# Chassis_Board.net
KiCad netlist of a schematic drawn in EAGLE
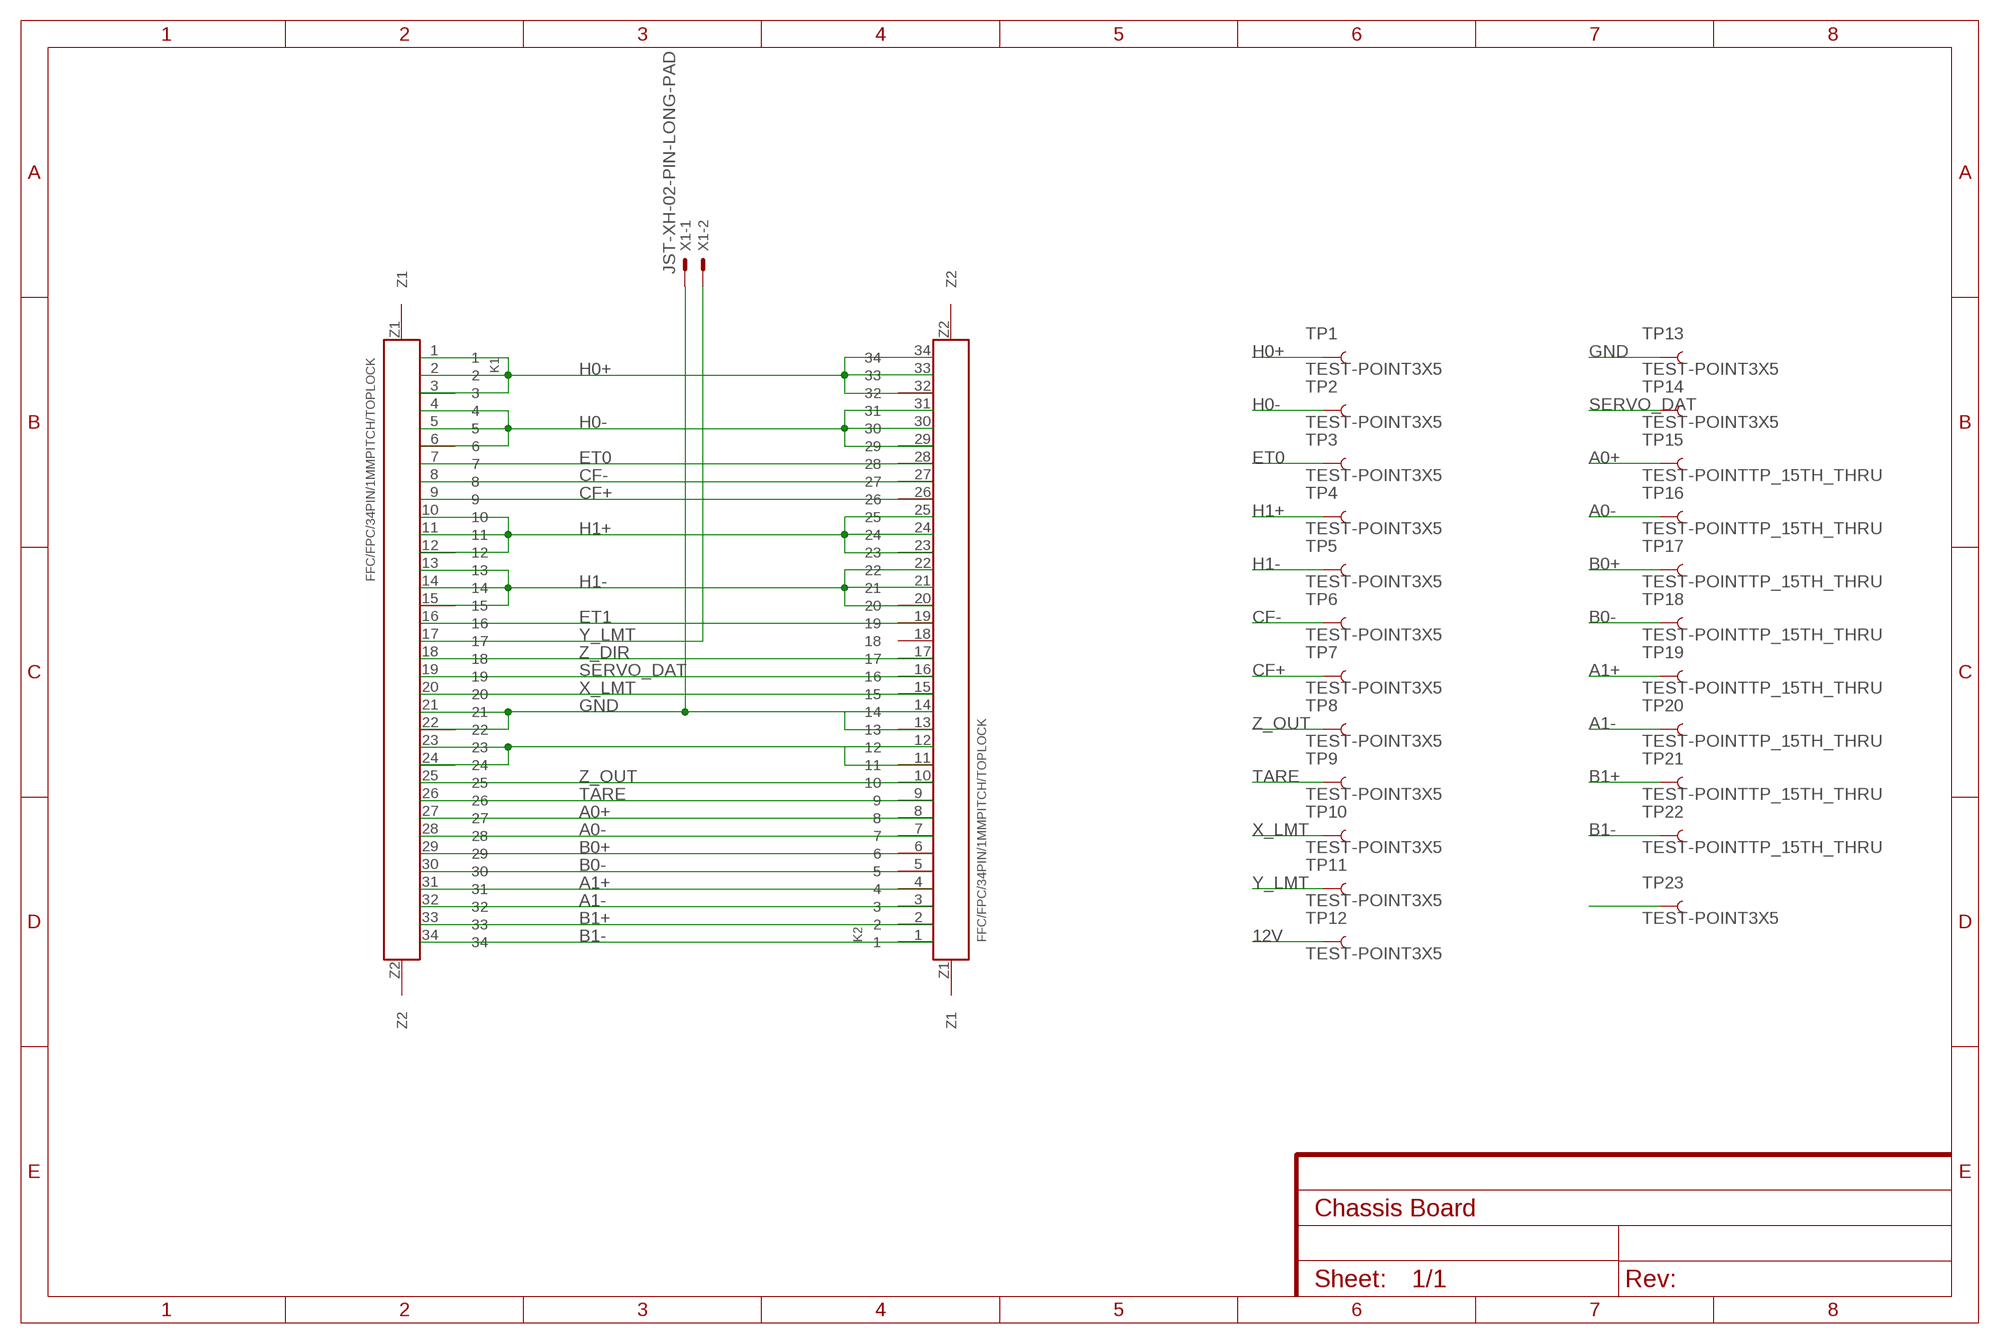
[diagram p0: schematic, sheet 1]

(export (version "E")
  (design (tool "Eeschema 10.0.6"))
  (components
    (comp (ref "K1")
      (value "FFC/FPC/34PIN/1MMPITCH/TOPLOCK")
      (footprint "eagle-import:34PIN_1MMPITCH_FFC_FPC")
      (libsource (lib "eagle-import") (part "FFC/FPC/34PIN/1MMPITCH/TOPLOCK"))
    )
    (comp (ref "K2")
      (value "FFC/FPC/34PIN/1MMPITCH/TOPLOCK")
      (footprint "eagle-import:34PIN_1MMPITCH_FFC_FPC")
      (libsource (lib "eagle-import") (part "FFC/FPC/34PIN/1MMPITCH/TOPLOCK"))
    )
    (comp (ref "TP1")
      (value "TEST-POINT3X5")
      (footprint "eagle-import:PAD.03X.05")
      (libsource (lib "eagle-import") (part "TEST-POINT3X5"))
    )
    (comp (ref "TP2")
      (value "TEST-POINT3X5")
      (footprint "eagle-import:PAD.03X.05")
      (libsource (lib "eagle-import") (part "TEST-POINT3X5"))
    )
    (comp (ref "TP3")
      (value "TEST-POINT3X5")
      (footprint "eagle-import:PAD.03X.05")
      (libsource (lib "eagle-import") (part "TEST-POINT3X5"))
    )
    (comp (ref "TP4")
      (value "TEST-POINT3X5")
      (footprint "eagle-import:PAD.03X.05")
      (libsource (lib "eagle-import") (part "TEST-POINT3X5"))
    )
    (comp (ref "TP5")
      (value "TEST-POINT3X5")
      (footprint "eagle-import:PAD.03X.05")
      (libsource (lib "eagle-import") (part "TEST-POINT3X5"))
    )
    (comp (ref "TP6")
      (value "TEST-POINT3X5")
      (footprint "eagle-import:PAD.03X.05")
      (libsource (lib "eagle-import") (part "TEST-POINT3X5"))
    )
    (comp (ref "TP7")
      (value "TEST-POINT3X5")
      (footprint "eagle-import:PAD.03X.05")
      (libsource (lib "eagle-import") (part "TEST-POINT3X5"))
    )
    (comp (ref "TP8")
      (value "TEST-POINT3X5")
      (footprint "eagle-import:PAD.03X.05")
      (libsource (lib "eagle-import") (part "TEST-POINT3X5"))
    )
    (comp (ref "TP9")
      (value "TEST-POINT3X5")
      (footprint "eagle-import:PAD.03X.05")
      (libsource (lib "eagle-import") (part "TEST-POINT3X5"))
    )
    (comp (ref "TP10")
      (value "TEST-POINT3X5")
      (footprint "eagle-import:PAD.03X.05")
      (libsource (lib "eagle-import") (part "TEST-POINT3X5"))
    )
    (comp (ref "TP11")
      (value "TEST-POINT3X5")
      (footprint "eagle-import:PAD.03X.05")
      (libsource (lib "eagle-import") (part "TEST-POINT3X5"))
    )
    (comp (ref "TP12")
      (value "TEST-POINT3X5")
      (footprint "eagle-import:PAD.03X.05")
      (libsource (lib "eagle-import") (part "TEST-POINT3X5"))
    )
    (comp (ref "TP13")
      (value "TEST-POINT3X5")
      (footprint "eagle-import:PAD.03X.05")
      (libsource (lib "eagle-import") (part "TEST-POINT3X5"))
    )
    (comp (ref "TP14")
      (value "TEST-POINT3X5")
      (footprint "eagle-import:PAD.03X.05")
      (libsource (lib "eagle-import") (part "TEST-POINT3X5"))
    )
    (comp (ref "TP15")
      (value "TEST-POINTTP_15TH_THRU")
      (footprint "eagle-import:TP_15TH")
      (libsource (lib "eagle-import") (part "TEST-POINTTP_15TH_THRU"))
    )
    (comp (ref "TP16")
      (value "TEST-POINTTP_15TH_THRU")
      (footprint "eagle-import:TP_15TH")
      (libsource (lib "eagle-import") (part "TEST-POINTTP_15TH_THRU"))
    )
    (comp (ref "TP17")
      (value "TEST-POINTTP_15TH_THRU")
      (footprint "eagle-import:TP_15TH")
      (libsource (lib "eagle-import") (part "TEST-POINTTP_15TH_THRU"))
    )
    (comp (ref "TP18")
      (value "TEST-POINTTP_15TH_THRU")
      (footprint "eagle-import:TP_15TH")
      (libsource (lib "eagle-import") (part "TEST-POINTTP_15TH_THRU"))
    )
    (comp (ref "TP19")
      (value "TEST-POINTTP_15TH_THRU")
      (footprint "eagle-import:TP_15TH")
      (libsource (lib "eagle-import") (part "TEST-POINTTP_15TH_THRU"))
    )
    (comp (ref "TP20")
      (value "TEST-POINTTP_15TH_THRU")
      (footprint "eagle-import:TP_15TH")
      (libsource (lib "eagle-import") (part "TEST-POINTTP_15TH_THRU"))
    )
    (comp (ref "TP21")
      (value "TEST-POINTTP_15TH_THRU")
      (footprint "eagle-import:TP_15TH")
      (libsource (lib "eagle-import") (part "TEST-POINTTP_15TH_THRU"))
    )
    (comp (ref "TP22")
      (value "TEST-POINTTP_15TH_THRU")
      (footprint "eagle-import:TP_15TH")
      (libsource (lib "eagle-import") (part "TEST-POINTTP_15TH_THRU"))
    )
    (comp (ref "TP23")
      (value "TEST-POINT3X5")
      (footprint "eagle-import:PAD.03X.05")
      (libsource (lib "eagle-import") (part "TEST-POINT3X5"))
    )
    (comp (ref "X1")
      (value "JST-XH-02-PIN-LONG-PAD")
      (footprint "eagle-import:JST-XH-02-PACKAGE-LONG-PAD")
      (libsource (lib "eagle-import") (part "JST-XH-02-PIN-LONG-PAD"))
    )
  )
  (nets
    (net (code "1") (name "/12V") (class "Default")
      (node (ref "K1") (pin "23") (pinfunction "23_23") (pintype "bidirectional"))
      (node (ref "K1") (pin "24") (pinfunction "24_24") (pintype "bidirectional"))
      (node (ref "K2") (pin "11") (pinfunction "11_11") (pintype "bidirectional"))
      (node (ref "K2") (pin "12") (pinfunction "12_12") (pintype "bidirectional"))
      (node (ref "TP12") (pin "P$1") (pinfunction "1_P$1") (pintype "bidirectional"))
    )
    (net (code "2") (name "/A0+") (class "Default")
      (node (ref "K1") (pin "27") (pinfunction "27_27") (pintype "bidirectional"))
      (node (ref "K2") (pin "8") (pinfunction "8_8") (pintype "bidirectional"))
      (node (ref "TP15") (pin "P$1") (pinfunction "1_P$1") (pintype "bidirectional"))
    )
    (net (code "3") (name "/A0-") (class "Default")
      (node (ref "K1") (pin "28") (pinfunction "28_28") (pintype "bidirectional"))
      (node (ref "K2") (pin "7") (pinfunction "7_7") (pintype "bidirectional"))
      (node (ref "TP16") (pin "P$1") (pinfunction "1_P$1") (pintype "bidirectional"))
    )
    (net (code "4") (name "/A1+") (class "Default")
      (node (ref "K1") (pin "31") (pinfunction "31_31") (pintype "bidirectional"))
      (node (ref "K2") (pin "4") (pinfunction "4_4") (pintype "bidirectional"))
      (node (ref "TP19") (pin "P$1") (pinfunction "1_P$1") (pintype "bidirectional"))
    )
    (net (code "5") (name "/A1-") (class "Default")
      (node (ref "K1") (pin "32") (pinfunction "32_32") (pintype "bidirectional"))
      (node (ref "K2") (pin "3") (pinfunction "3_3") (pintype "bidirectional"))
      (node (ref "TP20") (pin "P$1") (pinfunction "1_P$1") (pintype "bidirectional"))
    )
    (net (code "6") (name "/B0+") (class "Default")
      (node (ref "K1") (pin "29") (pinfunction "29_29") (pintype "bidirectional"))
      (node (ref "K2") (pin "6") (pinfunction "6_6") (pintype "bidirectional"))
      (node (ref "TP17") (pin "P$1") (pinfunction "1_P$1") (pintype "bidirectional"))
    )
    (net (code "7") (name "/B0-") (class "Default")
      (node (ref "K1") (pin "30") (pinfunction "30_30") (pintype "bidirectional"))
      (node (ref "K2") (pin "5") (pinfunction "5_5") (pintype "bidirectional"))
      (node (ref "TP18") (pin "P$1") (pinfunction "1_P$1") (pintype "bidirectional"))
    )
    (net (code "8") (name "/B1+") (class "Default")
      (node (ref "K1") (pin "33") (pinfunction "33_33") (pintype "bidirectional"))
      (node (ref "K2") (pin "2") (pinfunction "2_2") (pintype "bidirectional"))
      (node (ref "TP21") (pin "P$1") (pinfunction "1_P$1") (pintype "bidirectional"))
    )
    (net (code "9") (name "/B1-") (class "Default")
      (node (ref "K1") (pin "34") (pinfunction "34_34") (pintype "bidirectional"))
      (node (ref "K2") (pin "1") (pinfunction "1_1") (pintype "bidirectional"))
      (node (ref "TP22") (pin "P$1") (pinfunction "1_P$1") (pintype "bidirectional"))
    )
    (net (code "10") (name "/CF+") (class "Default")
      (node (ref "K1") (pin "9") (pinfunction "9_9") (pintype "bidirectional"))
      (node (ref "K2") (pin "26") (pinfunction "26_26") (pintype "bidirectional"))
      (node (ref "TP7") (pin "P$1") (pinfunction "1_P$1") (pintype "bidirectional"))
    )
    (net (code "11") (name "/CF-") (class "Default")
      (node (ref "K1") (pin "8") (pinfunction "8_8") (pintype "bidirectional"))
      (node (ref "K2") (pin "27") (pinfunction "27_27") (pintype "bidirectional"))
      (node (ref "TP6") (pin "P$1") (pinfunction "1_P$1") (pintype "bidirectional"))
    )
    (net (code "12") (name "/ET0") (class "Default")
      (node (ref "K1") (pin "7") (pinfunction "7_7") (pintype "bidirectional"))
      (node (ref "K2") (pin "28") (pinfunction "28_28") (pintype "bidirectional"))
      (node (ref "TP3") (pin "P$1") (pinfunction "1_P$1") (pintype "bidirectional"))
    )
    (net (code "13") (name "/ET1") (class "Default")
      (node (ref "K1") (pin "16") (pinfunction "16_16") (pintype "bidirectional"))
      (node (ref "K2") (pin "19") (pinfunction "19_19") (pintype "bidirectional"))
      (node (ref "TP23") (pin "P$1") (pinfunction "1_P$1") (pintype "bidirectional"))
    )
    (net (code "14") (name "/GND") (class "Default")
      (node (ref "K1") (pin "21") (pinfunction "21_21") (pintype "bidirectional"))
      (node (ref "K1") (pin "22") (pinfunction "22_22") (pintype "bidirectional"))
      (node (ref "K2") (pin "13") (pinfunction "13_13") (pintype "bidirectional"))
      (node (ref "K2") (pin "14") (pinfunction "14_14") (pintype "bidirectional"))
      (node (ref "TP13") (pin "P$1") (pinfunction "1_P$1") (pintype "bidirectional"))
      (node (ref "X1") (pin "1") (pinfunction "S_1") (pintype "passive"))
    )
    (net (code "15") (name "/H0+") (class "Default")
      (node (ref "K1") (pin "1") (pinfunction "1_1") (pintype "bidirectional"))
      (node (ref "K1") (pin "2") (pinfunction "2_2") (pintype "bidirectional"))
      (node (ref "K1") (pin "3") (pinfunction "3_3") (pintype "bidirectional"))
      (node (ref "K2") (pin "32") (pinfunction "32_32") (pintype "bidirectional"))
      (node (ref "K2") (pin "33") (pinfunction "33_33") (pintype "bidirectional"))
      (node (ref "K2") (pin "34") (pinfunction "34_34") (pintype "bidirectional"))
      (node (ref "TP1") (pin "P$1") (pinfunction "1_P$1") (pintype "bidirectional"))
    )
    (net (code "16") (name "/H0-") (class "Default")
      (node (ref "K1") (pin "4") (pinfunction "4_4") (pintype "bidirectional"))
      (node (ref "K1") (pin "5") (pinfunction "5_5") (pintype "bidirectional"))
      (node (ref "K1") (pin "6") (pinfunction "6_6") (pintype "bidirectional"))
      (node (ref "K2") (pin "29") (pinfunction "29_29") (pintype "bidirectional"))
      (node (ref "K2") (pin "30") (pinfunction "30_30") (pintype "bidirectional"))
      (node (ref "K2") (pin "31") (pinfunction "31_31") (pintype "bidirectional"))
      (node (ref "TP2") (pin "P$1") (pinfunction "1_P$1") (pintype "bidirectional"))
    )
    (net (code "17") (name "/H1+") (class "Default")
      (node (ref "K1") (pin "10") (pinfunction "10_10") (pintype "bidirectional"))
      (node (ref "K1") (pin "11") (pinfunction "11_11") (pintype "bidirectional"))
      (node (ref "K1") (pin "12") (pinfunction "12_12") (pintype "bidirectional"))
      (node (ref "K2") (pin "23") (pinfunction "23_23") (pintype "bidirectional"))
      (node (ref "K2") (pin "24") (pinfunction "24_24") (pintype "bidirectional"))
      (node (ref "K2") (pin "25") (pinfunction "25_25") (pintype "bidirectional"))
      (node (ref "TP4") (pin "P$1") (pinfunction "1_P$1") (pintype "bidirectional"))
    )
    (net (code "18") (name "/H1-") (class "Default")
      (node (ref "K1") (pin "13") (pinfunction "13_13") (pintype "bidirectional"))
      (node (ref "K1") (pin "14") (pinfunction "14_14") (pintype "bidirectional"))
      (node (ref "K1") (pin "15") (pinfunction "15_15") (pintype "bidirectional"))
      (node (ref "K2") (pin "20") (pinfunction "20_20") (pintype "bidirectional"))
      (node (ref "K2") (pin "21") (pinfunction "21_21") (pintype "bidirectional"))
      (node (ref "K2") (pin "22") (pinfunction "22_22") (pintype "bidirectional"))
      (node (ref "TP5") (pin "P$1") (pinfunction "1_P$1") (pintype "bidirectional"))
    )
    (net (code "19") (name "/SERVO_DAT") (class "Default")
      (node (ref "K1") (pin "19") (pinfunction "19_19") (pintype "bidirectional"))
      (node (ref "K2") (pin "16") (pinfunction "16_16") (pintype "bidirectional"))
      (node (ref "TP14") (pin "P$1") (pinfunction "1_P$1") (pintype "bidirectional"))
    )
    (net (code "20") (name "/TARE") (class "Default")
      (node (ref "K1") (pin "26") (pinfunction "26_26") (pintype "bidirectional"))
      (node (ref "K2") (pin "9") (pinfunction "9_9") (pintype "bidirectional"))
      (node (ref "TP9") (pin "P$1") (pinfunction "1_P$1") (pintype "bidirectional"))
    )
    (net (code "21") (name "/X_LMT") (class "Default")
      (node (ref "K1") (pin "20") (pinfunction "20_20") (pintype "bidirectional"))
      (node (ref "K2") (pin "15") (pinfunction "15_15") (pintype "bidirectional"))
      (node (ref "TP10") (pin "P$1") (pinfunction "1_P$1") (pintype "bidirectional"))
    )
    (net (code "22") (name "/Y_LMT") (class "Default")
      (node (ref "K1") (pin "17") (pinfunction "17_17") (pintype "bidirectional"))
      (node (ref "TP11") (pin "P$1") (pinfunction "1_P$1") (pintype "bidirectional"))
      (node (ref "X1") (pin "2") (pinfunction "S_2") (pintype "passive"))
    )
    (net (code "23") (name "/Z_DIR") (class "Default")
      (node (ref "K1") (pin "18") (pinfunction "18_18") (pintype "bidirectional"))
      (node (ref "K2") (pin "17") (pinfunction "17_17") (pintype "bidirectional"))
    )
    (net (code "24") (name "/Z_OUT") (class "Default")
      (node (ref "K1") (pin "25") (pinfunction "25_25") (pintype "bidirectional"))
      (node (ref "K2") (pin "10") (pinfunction "10_10") (pintype "bidirectional"))
      (node (ref "TP8") (pin "P$1") (pinfunction "1_P$1") (pintype "bidirectional"))
    )
    (net (code "25") (name "unconnected-(K1-PadZ1)") (class "Default")
      (node (ref "K1") (pin "Z1") (pinfunction "Z1_Z1") (pintype "bidirectional"))
    )
    (net (code "26") (name "unconnected-(K1-PadZ2)") (class "Default")
      (node (ref "K1") (pin "Z2") (pinfunction "Z2_Z2") (pintype "bidirectional"))
    )
    (net (code "27") (name "unconnected-(K2-Pad18)") (class "Default")
      (node (ref "K2") (pin "18") (pinfunction "18_18") (pintype "bidirectional"))
    )
    (net (code "28") (name "unconnected-(K2-PadZ1)") (class "Default")
      (node (ref "K2") (pin "Z1") (pinfunction "Z1_Z1") (pintype "bidirectional"))
    )
    (net (code "29") (name "unconnected-(K2-PadZ2)") (class "Default")
      (node (ref "K2") (pin "Z2") (pinfunction "Z2_Z2") (pintype "bidirectional"))
    )
  )
)
